# cv-pots.net
KiCad netlist of a schematic drawn in EAGLE
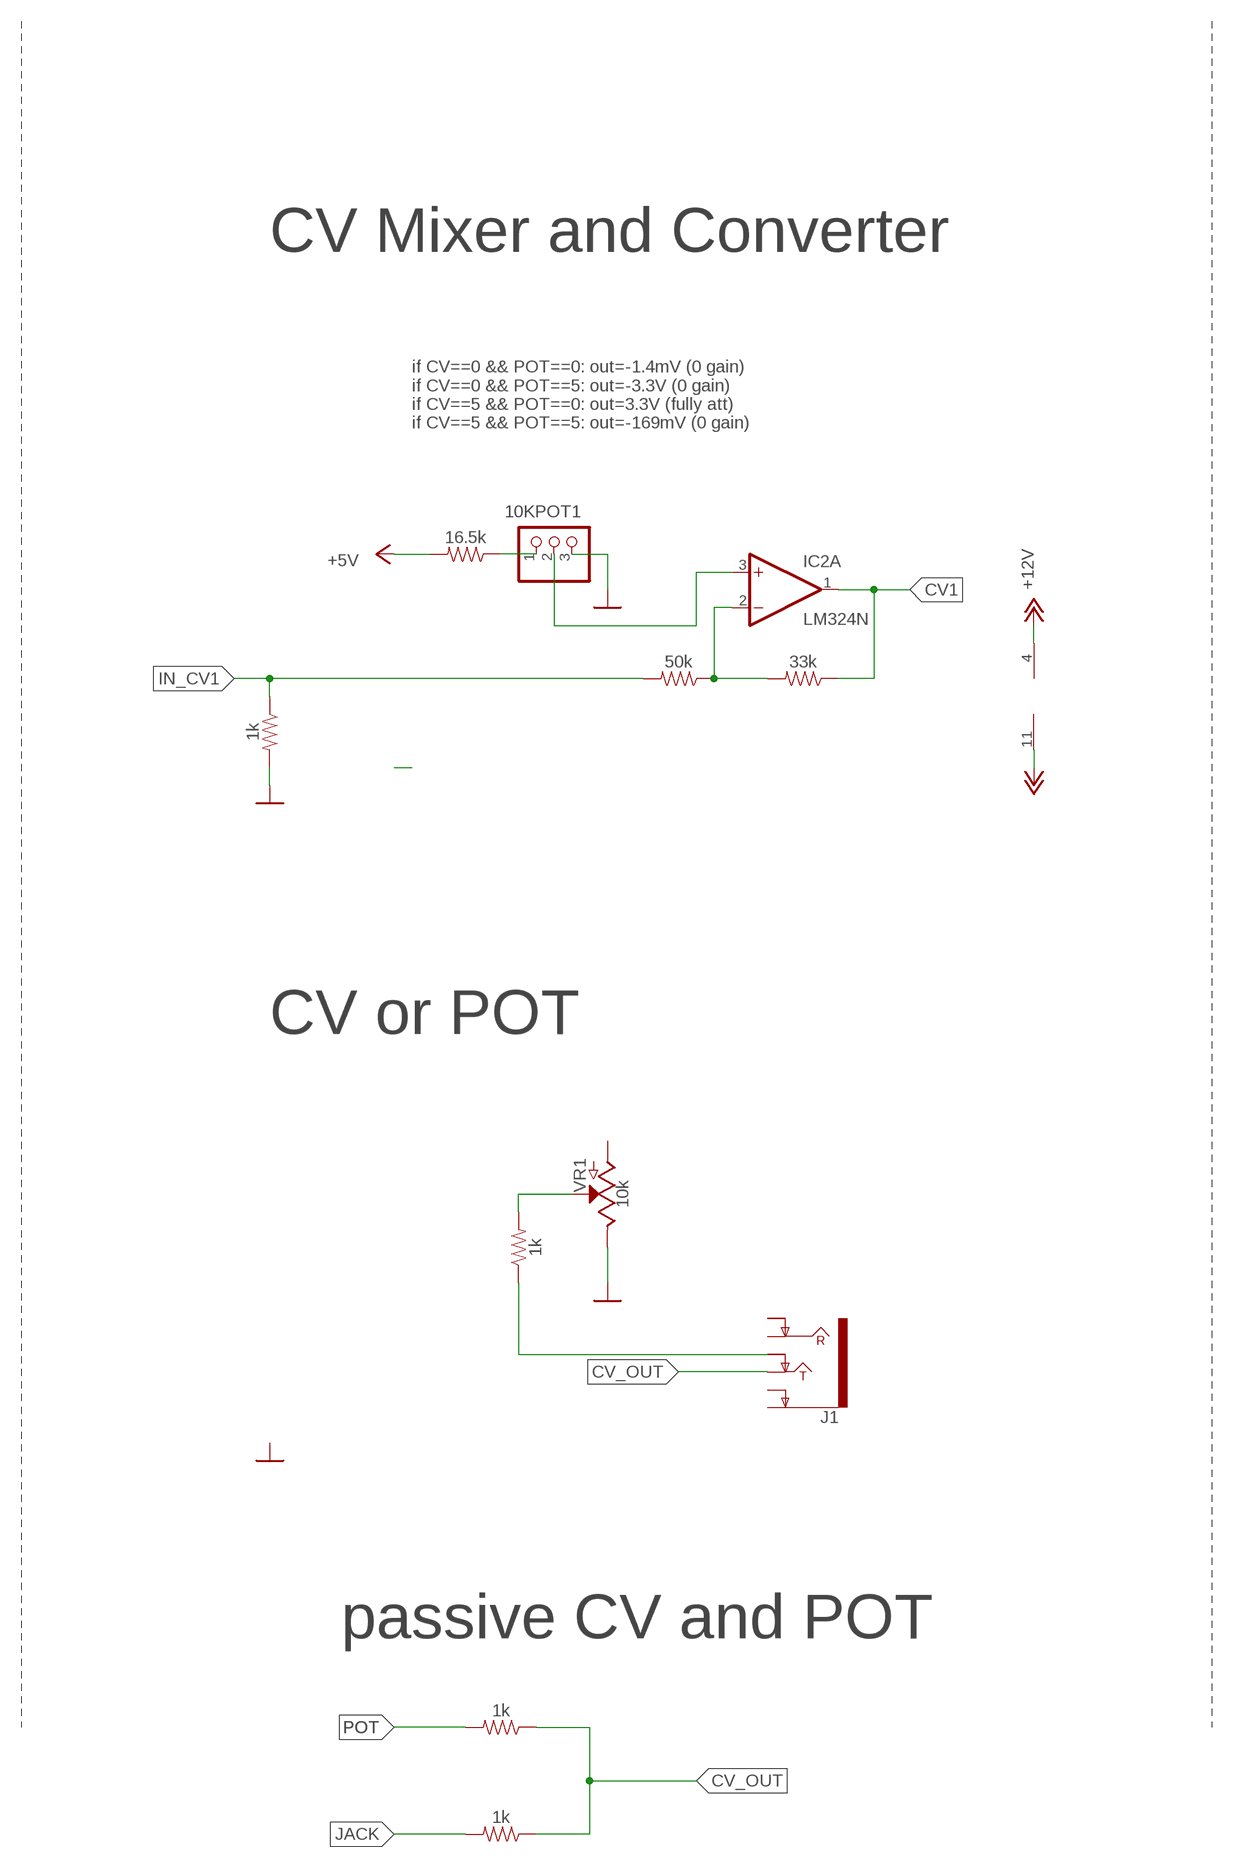
[diagram p0: schematic, sheet 1]

(export (version "E")
  (design (tool "Eeschema 10.0.6"))
  (components
    (comp (ref "10KPOT1")
      (value "PINHD-1X3")
      (footprint "eagle-import:1X03")
      (libsource (lib "eagle-import") (part "PINHD-1X3"))
    )
    (comp (ref "IC2")
      (value "LM324N")
      (footprint "eagle-import:DIL14")
      (libsource (lib "eagle-import") (part "LM324N"))
    )
    (comp (ref "J1")
      (value "AUDIO_JACK_TRS_0.25\"_PTH_RA")
      (footprint "eagle-import:AUDIO_JACK_0.25__TRS_PTH_RA")
      (libsource (lib "eagle-import") (part "AUDIO_JACK_TRS_0.25{dblquote}_PTH_RA"))
    )
    (comp (ref "R1")
      (value "1k")
      (footprint "eagle-import:AXIAL-0.3")
      (libsource (lib "eagle-import") (part "RESISTORAXIAL-0.3"))
    )
    (comp (ref "R2")
      (value "1k")
      (footprint "eagle-import:AXIAL-0.3")
      (libsource (lib "eagle-import") (part "RESISTORAXIAL-0.3"))
    )
    (comp (ref "R3")
      (value "1k")
      (footprint "eagle-import:AXIAL-0.3")
      (libsource (lib "eagle-import") (part "RESISTORAXIAL-0.3"))
    )
    (comp (ref "R9")
      (value "1k")
      (footprint "eagle-import:AXIAL-0.3")
      (libsource (lib "eagle-import") (part "RESISTORAXIAL-0.3"))
    )
    (comp (ref "R18")
      (value "16.5k")
      (footprint "eagle-import:AXIAL-0.3")
      (libsource (lib "eagle-import") (part "RESISTORAXIAL-0.3"))
    )
    (comp (ref "R19")
      (value "50k")
      (footprint "eagle-import:AXIAL-0.3")
      (libsource (lib "eagle-import") (part "RESISTORAXIAL-0.3"))
    )
    (comp (ref "R20")
      (value "33k")
      (footprint "eagle-import:AXIAL-0.3")
      (libsource (lib "eagle-import") (part "RESISTORAXIAL-0.3"))
    )
    (comp (ref "VR1")
      (value "10k")
      (footprint "eagle-import:POT-PTH-ALPS")
      (libsource (lib "eagle-import") (part "POTENTIOMETER-PTH-9MM-1/20W-20%"))
    )
  )
  (nets
    (net (code "1") (name "+5V") (class "Default")
      (node (ref "R18") (pin "P$2") (pinfunction "2_P$2") (pintype "passive"))
    )
    (net (code "2") (name "+12V") (class "Default")
      (node (ref "IC2") (pin "4") (pinfunction "V+_4") (pintype "power_in"))
    )
    (net (code "3") (name "-12V") (class "Default")
      (node (ref "IC2") (pin "11") (pinfunction "V-_11") (pintype "power_in"))
    )
    (net (code "4") (name "CV1") (class "Default")
      (node (ref "IC2") (pin "1") (pinfunction "OUT_1") (pintype "output"))
      (node (ref "R20") (pin "P$1") (pinfunction "1_P$1") (pintype "passive"))
    )
    (net (code "5") (name "CV_OUT") (class "Default")
      (node (ref "J1") (pin "TIP") (pinfunction "TIP_TIP") (pintype "bidirectional"))
      (node (ref "R2") (pin "P$1") (pinfunction "1_P$1") (pintype "passive"))
      (node (ref "R3") (pin "P$1") (pinfunction "1_P$1") (pintype "passive"))
    )
    (net (code "6") (name "GND") (class "Default")
      (node (ref "10KPOT1") (pin "3") (pinfunction "3_3") (pintype "passive"))
      (node (ref "R9") (pin "P$2") (pinfunction "2_P$2") (pintype "passive"))
      (node (ref "VR1") (pin "P$1") (pinfunction "E_P$1") (pintype "passive"))
    )
    (net (code "7") (name "IN_CV1") (class "Default")
      (node (ref "R19") (pin "P$2") (pinfunction "2_P$2") (pintype "passive"))
      (node (ref "R9") (pin "P$1") (pinfunction "1_P$1") (pintype "passive"))
    )
    (net (code "8") (name "JACK") (class "Default")
      (node (ref "R3") (pin "P$2") (pinfunction "2_P$2") (pintype "passive"))
    )
    (net (code "9") (name "Net-(IC2A-+IN)") (class "Default")
      (node (ref "10KPOT1") (pin "2") (pinfunction "2_2") (pintype "passive"))
      (node (ref "IC2") (pin "3") (pinfunction "+IN_3") (pintype "input"))
    )
    (net (code "10") (name "Net-(IC2A--IN)") (class "Default")
      (node (ref "IC2") (pin "2") (pinfunction "-IN_2") (pintype "input"))
      (node (ref "R19") (pin "P$1") (pinfunction "1_P$1") (pintype "passive"))
      (node (ref "R20") (pin "P$2") (pinfunction "2_P$2") (pintype "passive"))
    )
    (net (code "11") (name "Net-(R1-1)") (class "Default")
      (node (ref "J1") (pin "TIP-NORM") (pinfunction "TIP-NORM_TIP-NORM") (pintype "bidirectional"))
      (node (ref "R1") (pin "P$1") (pinfunction "1_P$1") (pintype "passive"))
    )
    (net (code "12") (name "Net-(R1-2)") (class "Default")
      (node (ref "R1") (pin "P$2") (pinfunction "2_P$2") (pintype "passive"))
      (node (ref "VR1") (pin "P$2") (pinfunction "S_P$2") (pintype "passive"))
    )
    (net (code "13") (name "Net-(R18-1)") (class "Default")
      (node (ref "10KPOT1") (pin "1") (pinfunction "1_1") (pintype "passive"))
      (node (ref "R18") (pin "P$1") (pinfunction "1_P$1") (pintype "passive"))
    )
    (net (code "14") (name "POT") (class "Default")
      (node (ref "R2") (pin "P$2") (pinfunction "2_P$2") (pintype "passive"))
    )
    (net (code "15") (name "unconnected-(J1-EARTH-NORM-PadSLEEVE-NORM)") (class "Default")
      (node (ref "J1") (pin "SLEEVE-NORM") (pinfunction "EARTH-NORM_SLEEVE-NORM") (pintype "bidirectional"))
    )
    (net (code "16") (name "unconnected-(J1-EARTH-PadSLEEVE)") (class "Default")
      (node (ref "J1") (pin "SLEEVE") (pinfunction "EARTH_SLEEVE") (pintype "bidirectional"))
    )
    (net (code "17") (name "unconnected-(J1-PadRING)") (class "Default")
      (node (ref "J1") (pin "RING") (pinfunction "RING_RING") (pintype "bidirectional"))
    )
    (net (code "18") (name "unconnected-(J1-PadRING-NORM)") (class "Default")
      (node (ref "J1") (pin "RING-NORM") (pinfunction "RING-NORM_RING-NORM") (pintype "bidirectional"))
    )
    (net (code "19") (name "unconnected-(VR1-A-PadP$3)") (class "Default")
      (node (ref "VR1") (pin "P$3") (pinfunction "A_P$3") (pintype "passive"))
    )
  )
)
